# Sheet2.net
KiCad netlist of a schematic drawn in Altium Designer
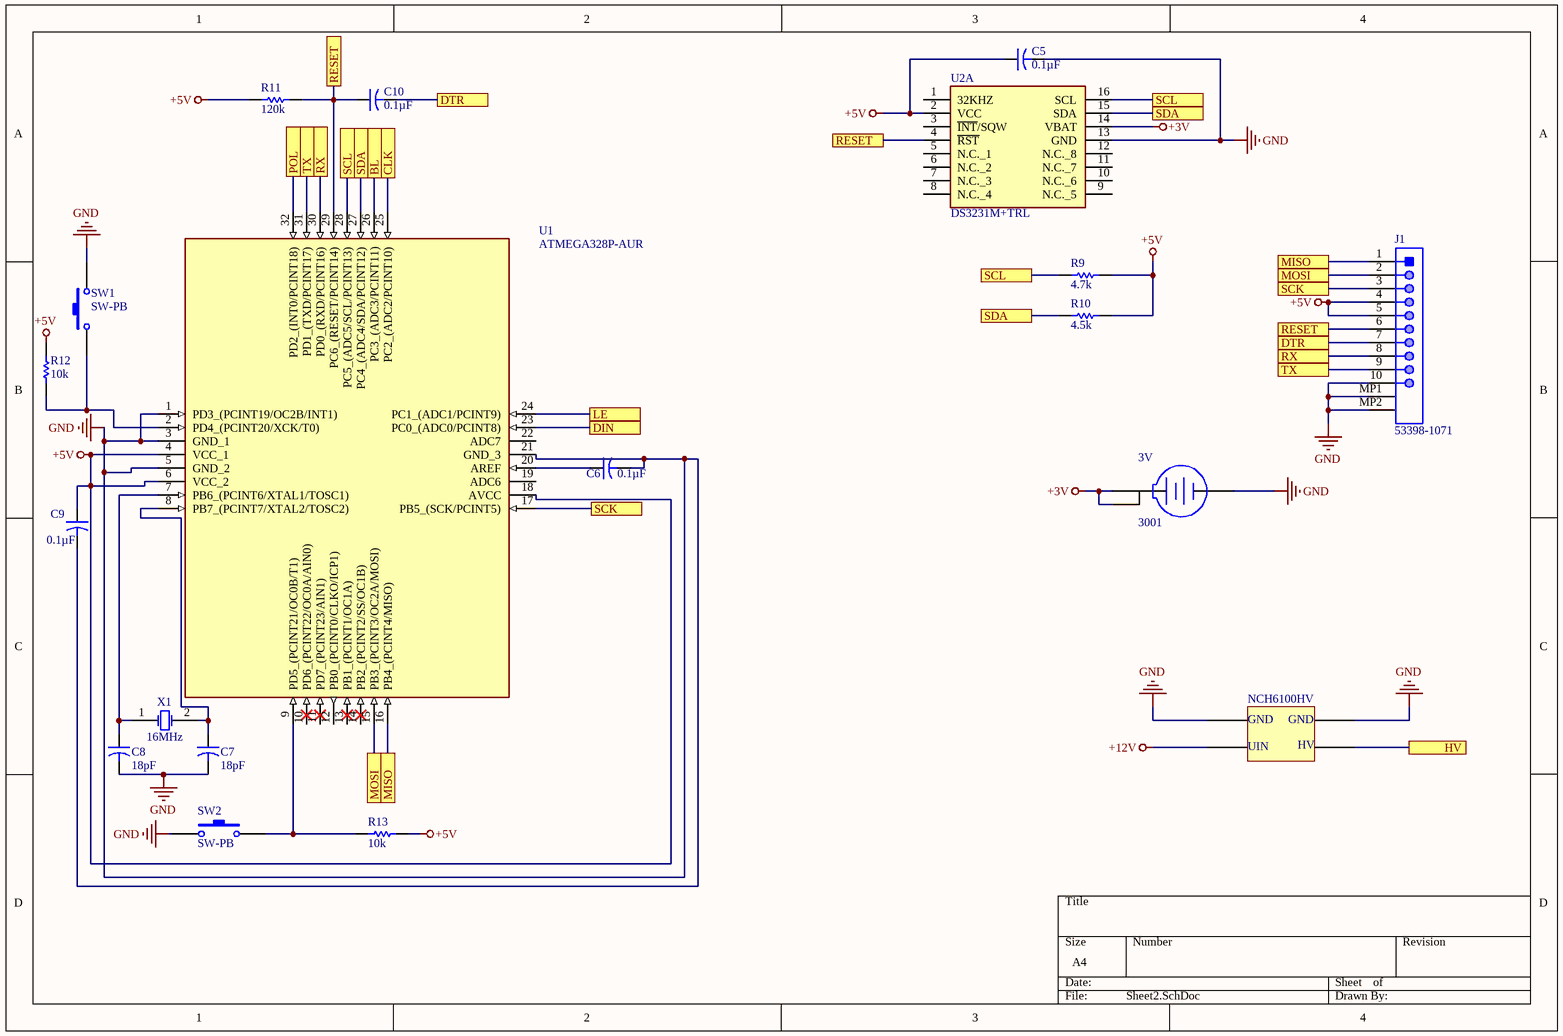
[diagram p0: Sheet2.SchDoc]

(export (version "E")
  (design (tool "Eeschema 10.0.6"))
  (components
    (comp (ref "3V")
      (value "3001")
      (footprint "KSTN-3001_V")
      (description "Holder Battery Coin, 12 mm, 2-Pin THD, RoHS")
      (fields (field (name "MANUFACTURER") "Keystone"))
      (libsource (lib "Altium Content Vault") (part "BATTERY-HOLDER-COIN-3"))
    )
    (comp (ref "C5")
      (value "0.1µF")
      (footprint "CAPR5-4X5")
      (description "Capacitor")
      (fields (field (name "PUBLISHER") "Altium Limited"))
      (libsource (lib "Miscellaneous Devices") (part "Cap2"))
    )
    (comp (ref "C6")
      (value "0.1µF")
      (footprint "CAPR5-4X5")
      (description "Capacitor")
      (fields (field (name "PUBLISHER") "Altium Limited"))
      (libsource (lib "Miscellaneous Devices") (part "Cap2"))
    )
    (comp (ref "C7")
      (value "18pF")
      (footprint "CAPR5-4X5")
      (description "Capacitor")
      (fields (field (name "PUBLISHER") "Altium Limited"))
      (libsource (lib "Miscellaneous Devices") (part "Cap2"))
    )
    (comp (ref "C8")
      (value "18pF")
      (footprint "CAPR5-4X5")
      (description "Capacitor")
      (fields (field (name "PUBLISHER") "Altium Limited"))
      (libsource (lib "Miscellaneous Devices") (part "Cap2"))
    )
    (comp (ref "C9")
      (value "0.1µF")
      (footprint "CAPR5-4X5")
      (description "Capacitor")
      (fields (field (name "PUBLISHER") "Altium Limited"))
      (libsource (lib "Miscellaneous Devices") (part "Cap2"))
    )
    (comp (ref "C10")
      (value "0.1µF")
      (footprint "CAPR5-4X5")
      (description "Capacitor")
      (fields (field (name "PUBLISHER") "Altium Limited"))
      (libsource (lib "Miscellaneous Devices") (part "Cap2"))
    )
    (comp (ref "J1")
      (value "53398-1071")
      (footprint "MOLX-53398-1071_V")
      (description "Male Header, Pitch 1.25 mm, 1 x 10 Position, Height 4.7 mm, -40 to 85 degC, RoHS, Tape and Reel")
      (fields (field (name "MANUFACTURER") "Molex"))
      (libsource (lib "Altium Content Vault") (part "CN-1P-2M-R10"))
    )
    (comp (ref "NCH6100HV")
      (value "NCH6100HV")
      (footprint "NCH6100HV")
      (libsource (lib "Schlib1") (part "NCH6100HV"))
    )
    (comp (ref "R9")
      (value "4.7k")
      (footprint "AXIAL-0.3")
      (description "Resistor")
      (fields (field (name "PUBLISHER") "Altium Limited"))
      (libsource (lib "Miscellaneous Devices") (part "Res1"))
    )
    (comp (ref "R10")
      (value "4.5k")
      (footprint "AXIAL-0.3")
      (description "Resistor")
      (fields (field (name "PUBLISHER") "Altium Limited"))
      (libsource (lib "Miscellaneous Devices") (part "Res1"))
    )
    (comp (ref "R11")
      (value "120k")
      (footprint "AXIAL-0.3")
      (description "Resistor")
      (fields (field (name "PUBLISHER") "Altium Limited"))
      (libsource (lib "Miscellaneous Devices") (part "Res1"))
    )
    (comp (ref "R12")
      (value "10k")
      (footprint "AXIAL-0.3")
      (description "Resistor")
      (fields (field (name "PUBLISHER") "Altium Limited"))
      (libsource (lib "Miscellaneous Devices") (part "Res1"))
    )
    (comp (ref "R13")
      (value "10k")
      (footprint "AXIAL-0.3")
      (description "Resistor")
      (fields (field (name "PUBLISHER") "Altium Limited"))
      (libsource (lib "Miscellaneous Devices") (part "Res1"))
    )
    (comp (ref "SW1")
      (value "SW-PB")
      (footprint "SPST-2")
      (description "Switch")
      (fields (field (name "PUBLISHER") "Altium Limited"))
      (libsource (lib "Miscellaneous Devices") (part "SW-PB"))
    )
    (comp (ref "SW2")
      (value "SW-PB")
      (footprint "SPST-2")
      (description "Switch")
      (fields (field (name "PUBLISHER") "Altium Limited"))
      (libsource (lib "Miscellaneous Devices") (part "SW-PB"))
    )
    (comp (ref "U1")
      (value "ATMEGA328P-AUR")
      (footprint "SamacSys:QFP80P900X900X120-32N")
      (description "Integrated Circuit")
      (fields
        (field (name "MOUSER PART NUMBER") "556-ATMEGA328P-AUR")
        (field (name "RS PART NUMBER") "1773264P")
      )
      (libsource (lib "*") (part "ATMEGA328P-AUR"))
    )
    (comp (ref "U2A")
      (value "DS3231M+TRL")
      (footprint "SamacSys:SOIC127P1032X265-16N")
      (description "Integrated Circuit")
      (fields (field (name "MOUSER PART NUMBER") "700-DS3231M+TRL"))
      (libsource (lib "*") (part "DS3231M+TRL"))
    )
    (comp (ref "X1")
      (value "16MHz")
      (footprint "R38")
      (description "Crystal Oscillator")
      (fields (field (name "PUBLISHER") "Altium Limited"))
      (libsource (lib "Miscellaneous Devices") (part "XTAL"))
    )
  )
  (nets
    (net (code "1") (name "+3V") (class "Default")
      (node (ref "3V") (pin "1") (pinfunction "+_1") (pintype "passive"))
      (node (ref "3V") (pin "2") (pinfunction "+_2") (pintype "passive"))
      (node (ref "U2A") (pin "14") (pinfunction "VBAT_14") (pintype "passive"))
    )
    (net (code "2") (name "+5V") (class "Default")
      (node (ref "C5") (pin "1") (pinfunction "1_1") (pintype "passive"))
      (node (ref "C9") (pin "1") (pinfunction "1_1") (pintype "passive"))
      (node (ref "J1") (pin "4") (pinfunction "4_4") (pintype "passive"))
      (node (ref "J1") (pin "5") (pinfunction "5_5") (pintype "passive"))
      (node (ref "R10") (pin "2") (pinfunction "2_2") (pintype "passive"))
      (node (ref "R11") (pin "1") (pinfunction "1_1") (pintype "passive"))
      (node (ref "R12") (pin "2") (pinfunction "2_2") (pintype "passive"))
      (node (ref "R13") (pin "1") (pinfunction "1_1") (pintype "passive"))
      (node (ref "R9") (pin "2") (pinfunction "2_2") (pintype "passive"))
      (node (ref "U1") (pin "18") (pinfunction "AVCC_18") (pintype "power_in"))
      (node (ref "U1") (pin "4") (pinfunction "VCC_1_4") (pintype "power_in"))
      (node (ref "U1") (pin "6") (pinfunction "VCC_2_6") (pintype "power_in"))
      (node (ref "U2A") (pin "2") (pinfunction "VCC_2") (pintype "passive"))
    )
    (net (code "4") (name "/BL") (class "Default")
      (node (ref "U1") (pin "26") (pinfunction "PC3_(ADC3/PCINT11)_26") (pintype "input"))
    )
    (net (code "5") (name "/CLK") (class "Default")
      (node (ref "U1") (pin "25") (pinfunction "PC2_(ADC2/PCINT10)_25") (pintype "input"))
    )
    (net (code "6") (name "/DIN") (class "Default")
      (node (ref "U1") (pin "23") (pinfunction "PC0_(ADC0/PCINT8)_23") (pintype "input"))
    )
    (net (code "7") (name "/DTR") (class "Default")
      (node (ref "C10") (pin "2") (pinfunction "2_2") (pintype "passive"))
      (node (ref "J1") (pin "7") (pinfunction "7_7") (pintype "passive"))
    )
    (net (code "8") (name "/HV") (class "Default")
      (node (ref "NCH6100HV") (pin "22") (pinfunction "22_22") (pintype "passive"))
    )
    (net (code "9") (name "/LE") (class "Default")
      (node (ref "U1") (pin "24") (pinfunction "PC1_(ADC1/PCINT9)_24") (pintype "input"))
    )
    (net (code "10") (name "/MISO") (class "Default")
      (node (ref "J1") (pin "1") (pinfunction "1_1") (pintype "passive"))
      (node (ref "U1") (pin "16") (pinfunction "PB4_(PCINT4/MISO)_16") (pintype "input"))
    )
    (net (code "11") (name "/MOSI") (class "Default")
      (node (ref "J1") (pin "2") (pinfunction "2_2") (pintype "passive"))
      (node (ref "U1") (pin "15") (pinfunction "PB3_(PCINT3/OC2A/MOSI)_15") (pintype "input"))
    )
    (net (code "12") (name "/POL") (class "Default")
      (node (ref "U1") (pin "32") (pinfunction "PD2_(INT0/PCINT18)_32") (pintype "input"))
    )
    (net (code "13") (name "/RESET") (class "Default")
      (node (ref "C10") (pin "1") (pinfunction "1_1") (pintype "passive"))
      (node (ref "J1") (pin "6") (pinfunction "6_6") (pintype "passive"))
      (node (ref "R11") (pin "2") (pinfunction "2_2") (pintype "passive"))
      (node (ref "U1") (pin "29") (pinfunction "PC6_(RESET/PCINT14)_29") (pintype "input"))
      (node (ref "U2A") (pin "4") (pinfunction "~{RST}_4") (pintype "passive"))
    )
    (net (code "14") (name "/RX") (class "Default")
      (node (ref "J1") (pin "8") (pinfunction "8_8") (pintype "passive"))
      (node (ref "U1") (pin "30") (pinfunction "PD0_(RXD/PCINT16)_30") (pintype "input"))
    )
    (net (code "15") (name "/SCK") (class "Default")
      (node (ref "J1") (pin "3") (pinfunction "3_3") (pintype "passive"))
      (node (ref "U1") (pin "17") (pinfunction "PB5_(SCK/PCINT5)_17") (pintype "input"))
    )
    (net (code "16") (name "/SCL") (class "Default")
      (node (ref "R9") (pin "1") (pinfunction "1_1") (pintype "passive"))
      (node (ref "U1") (pin "28") (pinfunction "PC5_(ADC5/SCL/PCINT13)_28") (pintype "input"))
      (node (ref "U2A") (pin "16") (pinfunction "SCL_16") (pintype "passive"))
    )
    (net (code "17") (name "/SDA") (class "Default")
      (node (ref "R10") (pin "1") (pinfunction "1_1") (pintype "passive"))
      (node (ref "U1") (pin "27") (pinfunction "PC4_(ADC4/SDA/PCINT12)_27") (pintype "input"))
      (node (ref "U2A") (pin "15") (pinfunction "SDA_15") (pintype "passive"))
    )
    (net (code "18") (name "/TX") (class "Default")
      (node (ref "J1") (pin "9") (pinfunction "9_9") (pintype "passive"))
      (node (ref "U1") (pin "31") (pinfunction "PD1_(TXD/PCINT17)_31") (pintype "input"))
    )
    (net (code "19") (name "GND") (class "Default")
      (node (ref "3V") (pin "3") (pinfunction "-_3") (pintype "passive"))
      (node (ref "C5") (pin "2") (pinfunction "2_2") (pintype "passive"))
      (node (ref "C6") (pin "2") (pinfunction "2_2") (pintype "passive"))
      (node (ref "C7") (pin "2") (pinfunction "2_2") (pintype "passive"))
      (node (ref "C8") (pin "2") (pinfunction "2_2") (pintype "passive"))
      (node (ref "C9") (pin "2") (pinfunction "2_2") (pintype "passive"))
      (node (ref "J1") (pin "10") (pinfunction "10_10") (pintype "passive"))
      (node (ref "J1") (pin "MP1") (pinfunction "MP1_MP1") (pintype "passive"))
      (node (ref "J1") (pin "MP2") (pinfunction "MP2_MP2") (pintype "passive"))
      (node (ref "NCH6100HV") (pin "21") (pinfunction "21_21") (pintype "passive"))
      (node (ref "SW1") (pin "2") (pinfunction "2_2") (pintype "passive"))
      (node (ref "SW2") (pin "1") (pinfunction "1_1") (pintype "passive"))
      (node (ref "U1") (pin "1") (pinfunction "PD3_(PCINT19/OC2B/INT1)_1") (pintype "input"))
      (node (ref "U1") (pin "21") (pinfunction "GND_3_21") (pintype "power_in"))
      (node (ref "U1") (pin "3") (pinfunction "GND_1_3") (pintype "power_in"))
      (node (ref "U1") (pin "5") (pinfunction "GND_2_5") (pintype "power_in"))
      (node (ref "U2A") (pin "13") (pinfunction "GND_13") (pintype "passive"))
    )
    (net (code "20") (name "Net-(U1-AREF)") (class "Default")
      (node (ref "C6") (pin "1") (pinfunction "1_1") (pintype "passive"))
      (node (ref "U1") (pin "20") (pinfunction "AREF_20") (pintype "input"))
    )
    (net (code "21") (name "Net-(U1-PB6_(PCINT6{slash}XTAL1{slash}TOSC1))") (class "Default")
      (node (ref "C8") (pin "1") (pinfunction "1_1") (pintype "passive"))
      (node (ref "U1") (pin "7") (pinfunction "PB6_(PCINT6/XTAL1/TOSC1)_7") (pintype "input"))
      (node (ref "X1") (pin "1") (pinfunction "OSC1_1") (pintype "passive"))
    )
    (net (code "22") (name "Net-(U1-PB7_(PCINT7{slash}XTAL2{slash}TOSC2))") (class "Default")
      (node (ref "C7") (pin "1") (pinfunction "1_1") (pintype "passive"))
      (node (ref "U1") (pin "8") (pinfunction "PB7_(PCINT7/XTAL2/TOSC2)_8") (pintype "input"))
      (node (ref "X1") (pin "2") (pinfunction "OSC2_2") (pintype "passive"))
    )
    (net (code "23") (name "Net-(U1-PD4_(PCINT20{slash}XCK{slash}T0))") (class "Default")
      (node (ref "R12") (pin "1") (pinfunction "1_1") (pintype "passive"))
      (node (ref "SW1") (pin "1") (pinfunction "1_1") (pintype "passive"))
      (node (ref "U1") (pin "2") (pinfunction "PD4_(PCINT20/XCK/T0)_2") (pintype "input"))
    )
    (net (code "24") (name "Net-(U1-PD5_(PCINT21{slash}OC0B{slash}T1))") (class "Default")
      (node (ref "R13") (pin "2") (pinfunction "2_2") (pintype "passive"))
      (node (ref "SW2") (pin "2") (pinfunction "2_2") (pintype "passive"))
      (node (ref "U1") (pin "9") (pinfunction "PD5_(PCINT21/OC0B/T1)_9") (pintype "input"))
    )
    (net (code "25") (name "unconnected-(NCH6100HV-Pad19)") (class "Default")
      (node (ref "NCH6100HV") (pin "19") (pinfunction "19_19") (pintype "passive"))
    )
    (net (code "26") (name "unconnected-(NCH6100HV-Pad20)") (class "Default")
      (node (ref "NCH6100HV") (pin "20") (pinfunction "20_20") (pintype "passive"))
    )
    (net (code "27") (name "unconnected-(U1-ADC6-Pad19)") (class "Default")
      (node (ref "U1") (pin "19") (pinfunction "ADC6_19") (pintype "passive"))
    )
    (net (code "28") (name "unconnected-(U1-ADC7-Pad22)") (class "Default")
      (node (ref "U1") (pin "22") (pinfunction "ADC7_22") (pintype "passive"))
    )
    (net (code "29") (name "unconnected-(U1-PB0_(PCINT0{slash}CLKO{slash}ICP1)-Pad12)") (class "Default")
      (node (ref "U1") (pin "12") (pinfunction "PB0_(PCINT0/CLKO/ICP1)_12") (pintype "output"))
    )
    (net (code "30") (name "unconnected-(U1-PB1_(PCINT1{slash}OC1A)-Pad13)") (class "Default")
      (node (ref "U1") (pin "13") (pinfunction "PB1_(PCINT1/OC1A)_13") (pintype "input"))
    )
    (net (code "31") (name "unconnected-(U1-PB2_(PCINT2{slash}SS{slash}OC1B)-Pad14)") (class "Default")
      (node (ref "U1") (pin "14") (pinfunction "PB2_(PCINT2/SS/OC1B)_14") (pintype "input"))
    )
    (net (code "32") (name "unconnected-(U1-PD6_(PCINT22{slash}OC0A{slash}AIN0)-Pad10)") (class "Default")
      (node (ref "U1") (pin "10") (pinfunction "PD6_(PCINT22/OC0A/AIN0)_10") (pintype "input"))
    )
    (net (code "33") (name "unconnected-(U1-PD7_(PCINT23{slash}AIN1)-Pad11)") (class "Default")
      (node (ref "U1") (pin "11") (pinfunction "PD7_(PCINT23/AIN1)_11") (pintype "input"))
    )
    (net (code "34") (name "unconnected-(U2A-32KHZ-Pad1)") (class "Default")
      (node (ref "U2A") (pin "1") (pinfunction "32KHZ_1") (pintype "passive"))
    )
    (net (code "35") (name "unconnected-(U2A-N.C._1-Pad5)") (class "Default")
      (node (ref "U2A") (pin "5") (pinfunction "N.C._1_5") (pintype "passive"))
    )
    (net (code "36") (name "unconnected-(U2A-N.C._2-Pad6)") (class "Default")
      (node (ref "U2A") (pin "6") (pinfunction "N.C._2_6") (pintype "passive"))
    )
    (net (code "37") (name "unconnected-(U2A-N.C._3-Pad7)") (class "Default")
      (node (ref "U2A") (pin "7") (pinfunction "N.C._3_7") (pintype "passive"))
    )
    (net (code "38") (name "unconnected-(U2A-N.C._4-Pad8)") (class "Default")
      (node (ref "U2A") (pin "8") (pinfunction "N.C._4_8") (pintype "passive"))
    )
    (net (code "39") (name "unconnected-(U2A-N.C._5-Pad9)") (class "Default")
      (node (ref "U2A") (pin "9") (pinfunction "N.C._5_9") (pintype "passive"))
    )
    (net (code "40") (name "unconnected-(U2A-N.C._6-Pad10)") (class "Default")
      (node (ref "U2A") (pin "10") (pinfunction "N.C._6_10") (pintype "passive"))
    )
    (net (code "41") (name "unconnected-(U2A-N.C._7-Pad11)") (class "Default")
      (node (ref "U2A") (pin "11") (pinfunction "N.C._7_11") (pintype "passive"))
    )
    (net (code "42") (name "unconnected-(U2A-N.C._8-Pad12)") (class "Default")
      (node (ref "U2A") (pin "12") (pinfunction "N.C._8_12") (pintype "passive"))
    )
    (net (code "43") (name "unconnected-(U2A-~{INT}{slash}SQW-Pad3)") (class "Default")
      (node (ref "U2A") (pin "3") (pinfunction "~{INT}/SQW_3") (pintype "passive"))
    )
  )
)
